# 23005_6.net
KiCad netlist of a schematic drawn in Altium Designer
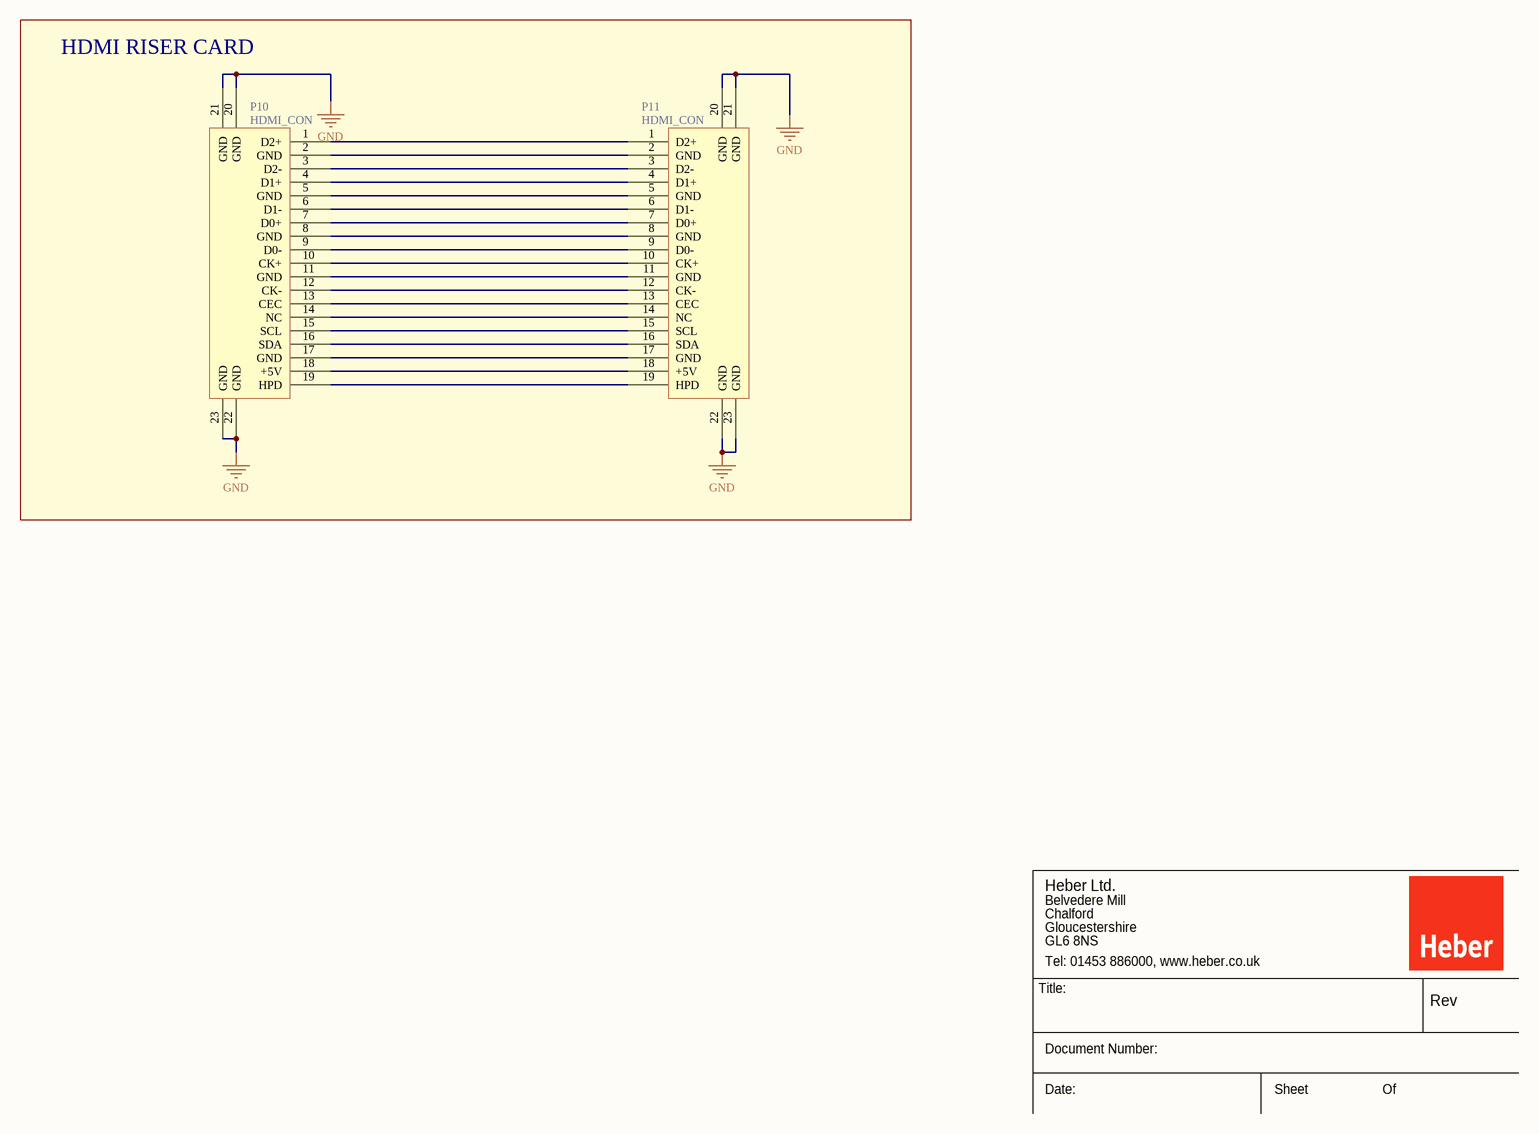
[diagram p0: 23005_6.SchDoc]

(export (version "E")
  (design (tool "Eeschema 10.0.6"))
  (components
    (comp (ref "P10") (value "HDMI_CON") (footprint "HDMI_VERT_PTH") (libsource (lib "") (part "HDMI_CON_1")))
    (comp (ref "P11")
      (value "HDMI_CON")
      (footprint "HDMI_VERT_PTH")
      (libsource (lib "LIBRARY1_Library") (part "HDMI_CON"))
    )
  )
  (nets
    (net (code "2") (name "GND") (class "Default")
      (node (ref "P10") (pin "20") (pinfunction "GND_20") (pintype "passive"))
      (node (ref "P10") (pin "21") (pinfunction "GND_21") (pintype "passive"))
      (node (ref "P10") (pin "22") (pinfunction "GND_22") (pintype "passive"))
      (node (ref "P10") (pin "23") (pinfunction "GND_23") (pintype "passive"))
      (node (ref "P11") (pin "20") (pinfunction "GND_20") (pintype "passive"))
      (node (ref "P11") (pin "21") (pinfunction "GND_21") (pintype "passive"))
      (node (ref "P11") (pin "22") (pinfunction "GND_22") (pintype "passive"))
      (node (ref "P11") (pin "23") (pinfunction "GND_23") (pintype "passive"))
    )
    (net (code "3") (name "Net-(P10-+5V)") (class "Default")
      (node (ref "P10") (pin "18") (pinfunction "+5V_18") (pintype "passive"))
      (node (ref "P11") (pin "18") (pinfunction "+5V_18") (pintype "passive"))
    )
    (net (code "4") (name "Net-(P10-CEC)") (class "Default")
      (node (ref "P10") (pin "13") (pinfunction "CEC_13") (pintype "passive"))
      (node (ref "P11") (pin "13") (pinfunction "CEC_13") (pintype "passive"))
    )
    (net (code "5") (name "Net-(P10-CK+)") (class "Default")
      (node (ref "P10") (pin "10") (pinfunction "CK+_10") (pintype "passive"))
      (node (ref "P11") (pin "10") (pinfunction "CK+_10") (pintype "passive"))
    )
    (net (code "6") (name "Net-(P10-CK-)") (class "Default")
      (node (ref "P10") (pin "12") (pinfunction "CK-_12") (pintype "passive"))
      (node (ref "P11") (pin "12") (pinfunction "CK-_12") (pintype "passive"))
    )
    (net (code "7") (name "Net-(P10-D0+)") (class "Default")
      (node (ref "P10") (pin "7") (pinfunction "D0+_7") (pintype "passive"))
      (node (ref "P11") (pin "7") (pinfunction "D0+_7") (pintype "passive"))
    )
    (net (code "8") (name "Net-(P10-D0-)") (class "Default")
      (node (ref "P10") (pin "9") (pinfunction "D0-_9") (pintype "passive"))
      (node (ref "P11") (pin "9") (pinfunction "D0-_9") (pintype "passive"))
    )
    (net (code "9") (name "Net-(P10-D1+)") (class "Default")
      (node (ref "P10") (pin "4") (pinfunction "D1+_4") (pintype "passive"))
      (node (ref "P11") (pin "4") (pinfunction "D1+_4") (pintype "passive"))
    )
    (net (code "10") (name "Net-(P10-D1-)") (class "Default")
      (node (ref "P10") (pin "6") (pinfunction "D1-_6") (pintype "passive"))
      (node (ref "P11") (pin "6") (pinfunction "D1-_6") (pintype "passive"))
    )
    (net (code "11") (name "Net-(P10-D2+)") (class "Default")
      (node (ref "P10") (pin "1") (pinfunction "D2+_1") (pintype "passive"))
      (node (ref "P11") (pin "1") (pinfunction "D2+_1") (pintype "passive"))
    )
    (net (code "12") (name "Net-(P10-D2-)") (class "Default")
      (node (ref "P10") (pin "3") (pinfunction "D2-_3") (pintype "passive"))
      (node (ref "P11") (pin "3") (pinfunction "D2-_3") (pintype "passive"))
    )
    (net (code "13") (name "Net-(P10-GND-Pad2)") (class "Default")
      (node (ref "P10") (pin "2") (pinfunction "GND_2") (pintype "passive"))
      (node (ref "P11") (pin "2") (pinfunction "GND_2") (pintype "passive"))
    )
    (net (code "14") (name "Net-(P10-GND-Pad5)") (class "Default")
      (node (ref "P10") (pin "5") (pinfunction "GND_5") (pintype "passive"))
      (node (ref "P11") (pin "5") (pinfunction "GND_5") (pintype "passive"))
    )
    (net (code "15") (name "Net-(P10-GND-Pad8)") (class "Default")
      (node (ref "P10") (pin "8") (pinfunction "GND_8") (pintype "passive"))
      (node (ref "P11") (pin "8") (pinfunction "GND_8") (pintype "passive"))
    )
    (net (code "16") (name "Net-(P10-GND-Pad11)") (class "Default")
      (node (ref "P10") (pin "11") (pinfunction "GND_11") (pintype "passive"))
      (node (ref "P11") (pin "11") (pinfunction "GND_11") (pintype "passive"))
    )
    (net (code "17") (name "Net-(P10-GND-Pad17)") (class "Default")
      (node (ref "P10") (pin "17") (pinfunction "GND_17") (pintype "passive"))
      (node (ref "P11") (pin "17") (pinfunction "GND_17") (pintype "passive"))
    )
    (net (code "18") (name "Net-(P10-HPD)") (class "Default")
      (node (ref "P10") (pin "19") (pinfunction "HPD_19") (pintype "passive"))
      (node (ref "P11") (pin "19") (pinfunction "HPD_19") (pintype "passive"))
    )
    (net (code "19") (name "Net-(P10-NC)") (class "Default")
      (node (ref "P10") (pin "14") (pinfunction "NC_14") (pintype "passive"))
      (node (ref "P11") (pin "14") (pinfunction "NC_14") (pintype "passive"))
    )
    (net (code "20") (name "Net-(P10-SCL)") (class "Default")
      (node (ref "P10") (pin "15") (pinfunction "SCL_15") (pintype "passive"))
      (node (ref "P11") (pin "15") (pinfunction "SCL_15") (pintype "passive"))
    )
    (net (code "21") (name "Net-(P10-SDA)") (class "Default")
      (node (ref "P10") (pin "16") (pinfunction "SDA_16") (pintype "passive"))
      (node (ref "P11") (pin "16") (pinfunction "SDA_16") (pintype "passive"))
    )
  )
)
